# IR-Blue_BT2_PCB.net
KiCad netlist of a schematic drawn in EAGLE
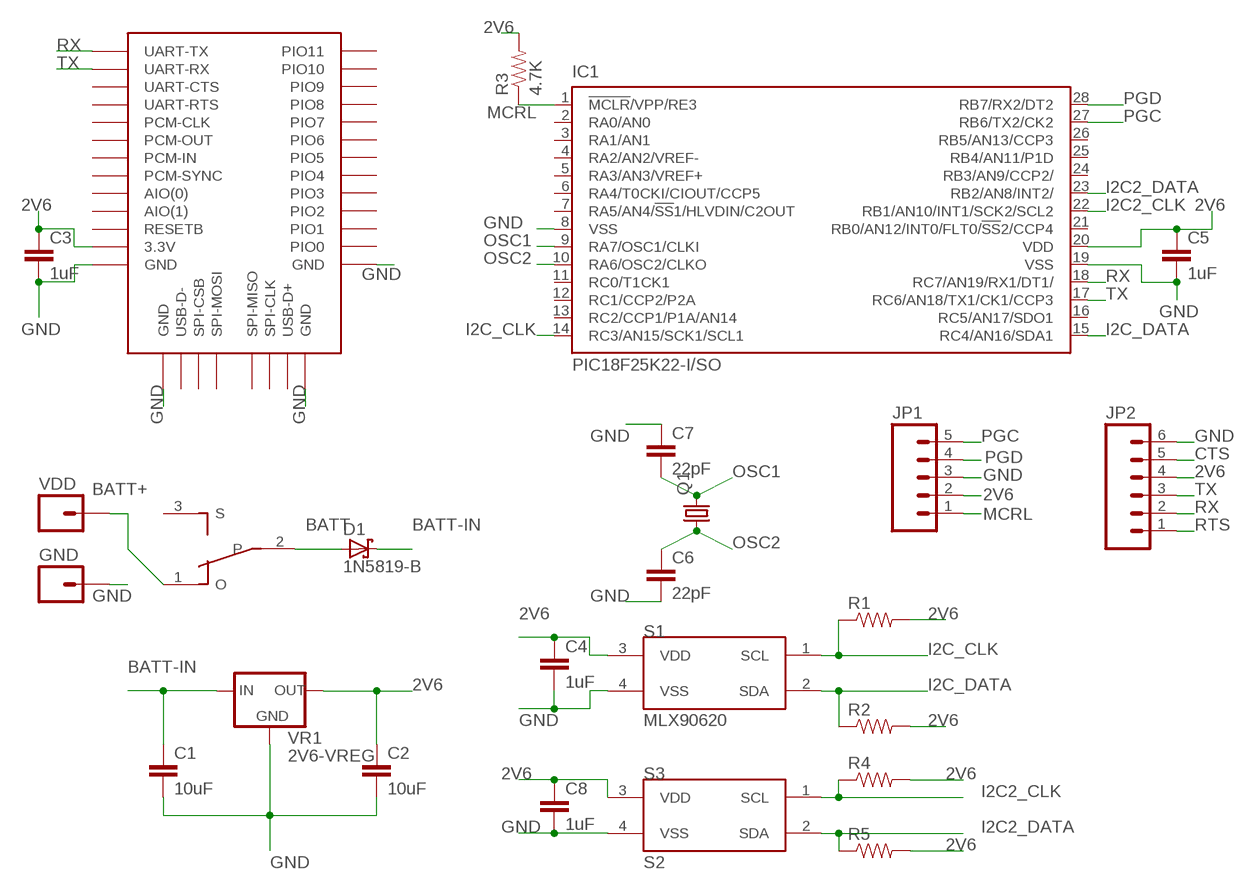
[diagram p0: schematic, sheet 1]

(export (version "E")
  (design (tool "Eeschema 10.0.6"))
  (components
    (comp (ref "C1")
      (value "10uF")
      (footprint "eagle-import:CAP-PTH-5MM")
      (libsource (lib "eagle-import") (part "CAPPTH1"))
    )
    (comp (ref "C2")
      (value "10uF")
      (footprint "eagle-import:CAP-PTH-5MM")
      (libsource (lib "eagle-import") (part "CAPPTH1"))
    )
    (comp (ref "C3")
      (value "1uF")
      (footprint "eagle-import:CAP-PTH-5MM")
      (libsource (lib "eagle-import") (part "CAPPTH1"))
    )
    (comp (ref "C4")
      (value "1uF")
      (footprint "eagle-import:CAP-PTH-5MM")
      (libsource (lib "eagle-import") (part "CAPPTH1"))
    )
    (comp (ref "C5")
      (value "1uF")
      (footprint "eagle-import:CAP-PTH-5MM")
      (libsource (lib "eagle-import") (part "CAPPTH1"))
    )
    (comp (ref "C6")
      (value "22pF")
      (footprint "eagle-import:CAP-PTH-5MM")
      (libsource (lib "eagle-import") (part "CAPPTH1"))
    )
    (comp (ref "C7")
      (value "22pF")
      (footprint "eagle-import:CAP-PTH-5MM")
      (libsource (lib "eagle-import") (part "CAPPTH1"))
    )
    (comp (ref "C8")
      (value "1uF")
      (footprint "eagle-import:CAP-PTH-5MM")
      (libsource (lib "eagle-import") (part "CAPPTH1"))
    )
    (comp (ref "D1")
      (value "1N5819-B")
      (footprint "eagle-import:DO41-7.6")
      (libsource (lib "eagle-import") (part "1N5819-B"))
    )
    (comp (ref "GND")
      (value "M01PTH")
      (footprint "eagle-import:1X01")
      (libsource (lib "eagle-import") (part "M01PTH"))
    )
    (comp (ref "IC1")
      (value "PIC18F25K22-I/SO")
      (footprint "eagle-import:SO28W")
      (libsource (lib "eagle-import") (part "PIC18F25K22/SO-I"))
    )
    (comp (ref "JP1")
      (value "M05PTH")
      (footprint "eagle-import:1X05")
      (libsource (lib "eagle-import") (part "M05PTH"))
    )
    (comp (ref "JP2")
      (value "M06SIP")
      (footprint "eagle-import:1X06")
      (libsource (lib "eagle-import") (part "M06SIP"))
    )
    (comp (ref "Q1")
      (value "CRYSTALHC49S")
      (footprint "eagle-import:HC49_S")
      (libsource (lib "eagle-import") (part "CRYSTALHC49S"))
    )
    (comp (ref "R1")
      (value "RESISTORPTH-1/4W")
      (footprint "eagle-import:AXIAL-0.4")
      (libsource (lib "eagle-import") (part "RESISTORPTH-1/4W"))
    )
    (comp (ref "R2")
      (value "RESISTORPTH-1/4W")
      (footprint "eagle-import:AXIAL-0.4")
      (libsource (lib "eagle-import") (part "RESISTORPTH-1/4W"))
    )
    (comp (ref "R3")
      (value "4.7K")
      (footprint "eagle-import:AXIAL-0.4")
      (libsource (lib "eagle-import") (part "RESISTORPTH-1/4W"))
    )
    (comp (ref "R4")
      (value "RESISTORPTH-1/4W")
      (footprint "eagle-import:AXIAL-0.4")
      (libsource (lib "eagle-import") (part "RESISTORPTH-1/4W"))
    )
    (comp (ref "R5")
      (value "RESISTORPTH-1/4W")
      (footprint "eagle-import:AXIAL-0.4")
      (libsource (lib "eagle-import") (part "RESISTORPTH-1/4W"))
    )
    (comp (ref "S1")
      (value "MLX90620")
      (footprint "eagle-import:TO-39")
      (libsource (lib "eagle-import") (part "MLX90620"))
    )
    (comp (ref "S3")
      (value "S2")
      (footprint "eagle-import:TO-39")
      (libsource (lib "eagle-import") (part "MLX90620"))
    )
    (comp (ref "SW1")
      (value "SMALL_SWITCH")
      (footprint "eagle-import:EG1213")
      (libsource (lib "eagle-import") (part "SMALL_SWITCH"))
    )
    (comp (ref "U$3")
      (value "BTM400_6B")
      (footprint "eagle-import:BTM400_6B")
      (libsource (lib "eagle-import") (part "BTM400_6B"))
    )
    (comp (ref "VDD")
      (value "M01PTH")
      (footprint "eagle-import:1X01")
      (libsource (lib "eagle-import") (part "M01PTH"))
    )
    (comp (ref "VR1")
      (value "2V6-VREG")
      (footprint "eagle-import:TO-92")
      (libsource (lib "eagle-import") (part "2V6-VREG"))
    )
  )
  (nets
    (net (code "1") (name "/2V6") (class "Default")
      (node (ref "C2") (pin "1") (pinfunction "1_1") (pintype "passive"))
      (node (ref "C3") (pin "1") (pinfunction "1_1") (pintype "passive"))
      (node (ref "C4") (pin "1") (pinfunction "1_1") (pintype "passive"))
      (node (ref "C5") (pin "1") (pinfunction "1_1") (pintype "passive"))
      (node (ref "C8") (pin "1") (pinfunction "1_1") (pintype "passive"))
      (node (ref "IC1") (pin "20") (pinfunction "VDD_20") (pintype "power_in"))
      (node (ref "JP1") (pin "2") (pinfunction "2_2") (pintype "passive"))
      (node (ref "JP2") (pin "4") (pinfunction "4_4") (pintype "passive"))
      (node (ref "R1") (pin "P$2") (pinfunction "2_P$2") (pintype "passive"))
      (node (ref "R2") (pin "P$2") (pinfunction "2_P$2") (pintype "passive"))
      (node (ref "R3") (pin "P$2") (pinfunction "2_P$2") (pintype "passive"))
      (node (ref "R4") (pin "P$2") (pinfunction "2_P$2") (pintype "passive"))
      (node (ref "R5") (pin "P$2") (pinfunction "2_P$2") (pintype "passive"))
      (node (ref "S1") (pin "3") (pinfunction "VDD_3") (pintype "bidirectional"))
      (node (ref "S3") (pin "3") (pinfunction "VDD_3") (pintype "bidirectional"))
      (node (ref "U$3") (pin "3.3V") (pinfunction "3.3V_3.3V") (pintype "power_in"))
      (node (ref "VR1") (pin "1") (pinfunction "OUT_1") (pintype "output"))
    )
    (net (code "2") (name "/BATT") (class "Default")
      (node (ref "D1") (pin "A") (pinfunction "A_A") (pintype "passive"))
      (node (ref "SW1") (pin "2") (pinfunction "P_2") (pintype "bidirectional"))
    )
    (net (code "3") (name "/BATT+") (class "Default")
      (node (ref "SW1") (pin "1") (pinfunction "O_1") (pintype "bidirectional"))
      (node (ref "VDD") (pin "1") (pinfunction "1_1") (pintype "passive"))
    )
    (net (code "4") (name "/BATT-IN") (class "Default")
      (node (ref "C1") (pin "1") (pinfunction "1_1") (pintype "passive"))
      (node (ref "D1") (pin "C") (pinfunction "C_C") (pintype "passive"))
      (node (ref "VR1") (pin "3") (pinfunction "IN_3") (pintype "input"))
    )
    (net (code "5") (name "/CTS") (class "Default")
      (node (ref "JP2") (pin "5") (pinfunction "5_5") (pintype "passive"))
    )
    (net (code "6") (name "/GND") (class "Default")
      (node (ref "C1") (pin "2") (pinfunction "2_2") (pintype "passive"))
      (node (ref "C2") (pin "2") (pinfunction "2_2") (pintype "passive"))
      (node (ref "C3") (pin "2") (pinfunction "2_2") (pintype "passive"))
      (node (ref "C4") (pin "2") (pinfunction "2_2") (pintype "passive"))
      (node (ref "C5") (pin "2") (pinfunction "2_2") (pintype "passive"))
      (node (ref "C6") (pin "2") (pinfunction "2_2") (pintype "passive"))
      (node (ref "C7") (pin "1") (pinfunction "1_1") (pintype "passive"))
      (node (ref "C8") (pin "2") (pinfunction "2_2") (pintype "passive"))
      (node (ref "GND") (pin "1") (pinfunction "1_1") (pintype "passive"))
      (node (ref "IC1") (pin "19") (pinfunction "VSS_19") (pintype "power_in"))
      (node (ref "IC1") (pin "8") (pinfunction "VSS_8") (pintype "power_in"))
      (node (ref "JP1") (pin "3") (pinfunction "3_3") (pintype "passive"))
      (node (ref "JP2") (pin "6") (pinfunction "6_6") (pintype "passive"))
      (node (ref "S1") (pin "4") (pinfunction "VSS_4") (pintype "bidirectional"))
      (node (ref "S3") (pin "4") (pinfunction "VSS_4") (pintype "bidirectional"))
      (node (ref "U$3") (pin "GND@1") (pinfunction "GND_GND@1") (pintype "power_in"))
      (node (ref "U$3") (pin "GND@2") (pinfunction "GND_GND@2") (pintype "power_in"))
      (node (ref "U$3") (pin "GND@3") (pinfunction "GND_GND@3") (pintype "power_in"))
      (node (ref "U$3") (pin "GND@4") (pinfunction "GND_GND@4") (pintype "power_in"))
      (node (ref "VR1") (pin "2") (pinfunction "GND_2") (pintype "input"))
    )
    (net (code "7") (name "/I2C2_CLK") (class "Default")
      (node (ref "IC1") (pin "22") (pinfunction "RB1/AN10/INT1/SCK2/SCL2_22") (pintype "bidirectional"))
      (node (ref "R4") (pin "P$1") (pinfunction "1_P$1") (pintype "passive"))
      (node (ref "S3") (pin "1") (pinfunction "SCL_1") (pintype "bidirectional"))
    )
    (net (code "8") (name "/I2C2_DATA") (class "Default")
      (node (ref "IC1") (pin "23") (pinfunction "RB2/AN8/INT2/_23") (pintype "bidirectional"))
      (node (ref "R5") (pin "P$1") (pinfunction "1_P$1") (pintype "passive"))
      (node (ref "S3") (pin "2") (pinfunction "SDA_2") (pintype "bidirectional"))
    )
    (net (code "9") (name "/I2C_CLK") (class "Default")
      (node (ref "IC1") (pin "14") (pinfunction "RC3/AN15/SCK1/SCL1_14") (pintype "bidirectional"))
      (node (ref "R1") (pin "P$1") (pinfunction "1_P$1") (pintype "passive"))
      (node (ref "S1") (pin "1") (pinfunction "SCL_1") (pintype "bidirectional"))
    )
    (net (code "10") (name "/I2C_DATA") (class "Default")
      (node (ref "IC1") (pin "15") (pinfunction "RC4/AN16/SDA1_15") (pintype "bidirectional"))
      (node (ref "R2") (pin "P$1") (pinfunction "1_P$1") (pintype "passive"))
      (node (ref "S1") (pin "2") (pinfunction "SDA_2") (pintype "bidirectional"))
    )
    (net (code "11") (name "/MCRL") (class "Default")
      (node (ref "IC1") (pin "1") (pinfunction "~{MCLR}/VPP/RE3_1") (pintype "input"))
      (node (ref "JP1") (pin "1") (pinfunction "1_1") (pintype "passive"))
      (node (ref "R3") (pin "P$1") (pinfunction "1_P$1") (pintype "passive"))
    )
    (net (code "12") (name "/OSC1") (class "Default")
      (node (ref "C7") (pin "2") (pinfunction "2_2") (pintype "passive"))
      (node (ref "IC1") (pin "9") (pinfunction "RA7/OSC1/CLKI_9") (pintype "input"))
      (node (ref "Q1") (pin "2") (pinfunction "2_2") (pintype "passive"))
    )
    (net (code "13") (name "/OSC2") (class "Default")
      (node (ref "C6") (pin "1") (pinfunction "1_1") (pintype "passive"))
      (node (ref "IC1") (pin "10") (pinfunction "RA6/OSC2/CLKO_10") (pintype "output"))
      (node (ref "Q1") (pin "1") (pinfunction "1_1") (pintype "passive"))
    )
    (net (code "14") (name "/PGC") (class "Default")
      (node (ref "IC1") (pin "27") (pinfunction "RB6/TX2/CK2_27") (pintype "bidirectional"))
      (node (ref "JP1") (pin "5") (pinfunction "5_5") (pintype "passive"))
    )
    (net (code "15") (name "/PGD") (class "Default")
      (node (ref "IC1") (pin "28") (pinfunction "RB7/RX2/DT2_28") (pintype "bidirectional"))
      (node (ref "JP1") (pin "4") (pinfunction "4_4") (pintype "passive"))
    )
    (net (code "16") (name "/RTS") (class "Default")
      (node (ref "JP2") (pin "1") (pinfunction "1_1") (pintype "passive"))
    )
    (net (code "17") (name "/RX") (class "Default")
      (node (ref "IC1") (pin "18") (pinfunction "RC7/AN19/RX1/DT1/_18") (pintype "bidirectional"))
      (node (ref "JP2") (pin "2") (pinfunction "2_2") (pintype "passive"))
      (node (ref "U$3") (pin "UART-TX") (pinfunction "UART-TX_UART-TX") (pintype "bidirectional"))
    )
    (net (code "18") (name "/TX") (class "Default")
      (node (ref "IC1") (pin "17") (pinfunction "RC6/AN18/TX1/CK1/CCP3_17") (pintype "bidirectional"))
      (node (ref "JP2") (pin "3") (pinfunction "3_3") (pintype "passive"))
      (node (ref "U$3") (pin "UART-RX") (pinfunction "UART-RX_UART-RX") (pintype "bidirectional"))
    )
    (net (code "19") (name "unconnected-(IC1-RA0{slash}AN0-Pad2)") (class "Default")
      (node (ref "IC1") (pin "2") (pinfunction "RA0/AN0_2") (pintype "bidirectional"))
    )
    (net (code "20") (name "unconnected-(IC1-RA1{slash}AN1-Pad3)") (class "Default")
      (node (ref "IC1") (pin "3") (pinfunction "RA1/AN1_3") (pintype "bidirectional"))
    )
    (net (code "21") (name "unconnected-(IC1-RA2{slash}AN2{slash}VREF--Pad4)") (class "Default")
      (node (ref "IC1") (pin "4") (pinfunction "RA2/AN2/VREF-_4") (pintype "bidirectional"))
    )
    (net (code "22") (name "unconnected-(IC1-RA3{slash}AN3{slash}VREF+-Pad5)") (class "Default")
      (node (ref "IC1") (pin "5") (pinfunction "RA3/AN3/VREF+_5") (pintype "bidirectional"))
    )
    (net (code "23") (name "unconnected-(IC1-RA4{slash}T0CKI{slash}CIOUT{slash}CCP5-Pad6)") (class "Default")
      (node (ref "IC1") (pin "6") (pinfunction "RA4/T0CKI/CIOUT/CCP5_6") (pintype "bidirectional"))
    )
    (net (code "24") (name "unconnected-(IC1-RA5{slash}AN4{slash}~{SS}1{slash}HLVDIN{slash}C2OUT-Pad7)") (class "Default")
      (node (ref "IC1") (pin "7") (pinfunction "RA5/AN4/~{SS}1/HLVDIN/C2OUT_7") (pintype "bidirectional"))
    )
    (net (code "25") (name "unconnected-(IC1-RB0{slash}AN12{slash}INT0{slash}FLT0{slash}~{SS}2{slash}CCP4-Pad21)") (class "Default")
      (node (ref "IC1") (pin "21") (pinfunction "RB0/AN12/INT0/FLT0/~{SS}2/CCP4_21") (pintype "bidirectional"))
    )
    (net (code "26") (name "unconnected-(IC1-RB3{slash}AN9{slash}CCP2{slash}-Pad24)") (class "Default")
      (node (ref "IC1") (pin "24") (pinfunction "RB3/AN9/CCP2/_24") (pintype "bidirectional"))
    )
    (net (code "27") (name "unconnected-(IC1-RB4{slash}AN11{slash}P1D-Pad25)") (class "Default")
      (node (ref "IC1") (pin "25") (pinfunction "RB4/AN11/P1D_25") (pintype "bidirectional"))
    )
    (net (code "28") (name "unconnected-(IC1-RB5{slash}AN13{slash}CCP3-Pad26)") (class "Default")
      (node (ref "IC1") (pin "26") (pinfunction "RB5/AN13/CCP3_26") (pintype "bidirectional"))
    )
    (net (code "29") (name "unconnected-(IC1-RC0{slash}T1CK1-Pad11)") (class "Default")
      (node (ref "IC1") (pin "11") (pinfunction "RC0/T1CK1_11") (pintype "bidirectional"))
    )
    (net (code "30") (name "unconnected-(IC1-RC1{slash}CCP2{slash}P2A-Pad12)") (class "Default")
      (node (ref "IC1") (pin "12") (pinfunction "RC1/CCP2/P2A_12") (pintype "bidirectional"))
    )
    (net (code "31") (name "unconnected-(IC1-RC2{slash}CCP1{slash}P1A{slash}AN14-Pad13)") (class "Default")
      (node (ref "IC1") (pin "13") (pinfunction "RC2/CCP1/P1A/AN14_13") (pintype "bidirectional"))
    )
    (net (code "32") (name "unconnected-(IC1-RC5{slash}AN17{slash}SDO1-Pad16)") (class "Default")
      (node (ref "IC1") (pin "16") (pinfunction "RC5/AN17/SDO1_16") (pintype "bidirectional"))
    )
    (net (code "33") (name "unconnected-(SW1-S-Pad3)") (class "Default")
      (node (ref "SW1") (pin "3") (pinfunction "S_3") (pintype "bidirectional"))
    )
    (net (code "34") (name "unconnected-(U$3-PIO0-PadPIO(0))") (class "Default")
      (node (ref "U$3") (pin "PIO(0)") (pinfunction "PIO0_PIO(0)") (pintype "bidirectional"))
    )
    (net (code "35") (name "unconnected-(U$3-PIO1-PadPIO(1))") (class "Default")
      (node (ref "U$3") (pin "PIO(1)") (pinfunction "PIO1_PIO(1)") (pintype "bidirectional"))
    )
    (net (code "36") (name "unconnected-(U$3-PIO2-PadPIO(2))") (class "Default")
      (node (ref "U$3") (pin "PIO(2)") (pinfunction "PIO2_PIO(2)") (pintype "bidirectional"))
    )
    (net (code "37") (name "unconnected-(U$3-PIO3-PadPIO(3))") (class "Default")
      (node (ref "U$3") (pin "PIO(3)") (pinfunction "PIO3_PIO(3)") (pintype "bidirectional"))
    )
    (net (code "38") (name "unconnected-(U$3-PIO4-PadPIO(4))") (class "Default")
      (node (ref "U$3") (pin "PIO(4)") (pinfunction "PIO4_PIO(4)") (pintype "bidirectional"))
    )
    (net (code "39") (name "unconnected-(U$3-PIO5-PadPIO(5))") (class "Default")
      (node (ref "U$3") (pin "PIO(5)") (pinfunction "PIO5_PIO(5)") (pintype "bidirectional"))
    )
    (net (code "40") (name "unconnected-(U$3-PIO6-PadPIO(6))") (class "Default")
      (node (ref "U$3") (pin "PIO(6)") (pinfunction "PIO6_PIO(6)") (pintype "bidirectional"))
    )
    (net (code "41") (name "unconnected-(U$3-PIO7-PadPIO(7))") (class "Default")
      (node (ref "U$3") (pin "PIO(7)") (pinfunction "PIO7_PIO(7)") (pintype "bidirectional"))
    )
    (net (code "42") (name "unconnected-(U$3-PIO8-PadPIO(8))") (class "Default")
      (node (ref "U$3") (pin "PIO(8)") (pinfunction "PIO8_PIO(8)") (pintype "bidirectional"))
    )
    (net (code "43") (name "unconnected-(U$3-PIO9-PadPIO(9))") (class "Default")
      (node (ref "U$3") (pin "PIO(9)") (pinfunction "PIO9_PIO(9)") (pintype "bidirectional"))
    )
    (net (code "44") (name "unconnected-(U$3-PIO10-PadPIO(10))") (class "Default")
      (node (ref "U$3") (pin "PIO(10)") (pinfunction "PIO10_PIO(10)") (pintype "bidirectional"))
    )
    (net (code "45") (name "unconnected-(U$3-PIO11-PadPIO(11))") (class "Default")
      (node (ref "U$3") (pin "PIO(11)") (pinfunction "PIO11_PIO(11)") (pintype "bidirectional"))
    )
    (net (code "46") (name "unconnected-(U$3-PadAIO(0))") (class "Default")
      (node (ref "U$3") (pin "AIO(0)") (pinfunction "AIO(0)_AIO(0)") (pintype "bidirectional"))
    )
    (net (code "47") (name "unconnected-(U$3-PadAIO(1))") (class "Default")
      (node (ref "U$3") (pin "AIO(1)") (pinfunction "AIO(1)_AIO(1)") (pintype "bidirectional"))
    )
    (net (code "48") (name "unconnected-(U$3-PadPCM-CLK)") (class "Default")
      (node (ref "U$3") (pin "PCM-CLK") (pinfunction "PCM-CLK_PCM-CLK") (pintype "bidirectional"))
    )
    (net (code "49") (name "unconnected-(U$3-PadPCM-IN)") (class "Default")
      (node (ref "U$3") (pin "PCM-IN") (pinfunction "PCM-IN_PCM-IN") (pintype "bidirectional"))
    )
    (net (code "50") (name "unconnected-(U$3-PadPCM-OUT)") (class "Default")
      (node (ref "U$3") (pin "PCM-OUT") (pinfunction "PCM-OUT_PCM-OUT") (pintype "bidirectional"))
    )
    (net (code "51") (name "unconnected-(U$3-PadPCM-SYNC)") (class "Default")
      (node (ref "U$3") (pin "PCM-SYNC") (pinfunction "PCM-SYNC_PCM-SYNC") (pintype "bidirectional"))
    )
    (net (code "52") (name "unconnected-(U$3-PadRESETB)") (class "Default")
      (node (ref "U$3") (pin "RESETB") (pinfunction "RESETB_RESETB") (pintype "bidirectional"))
    )
    (net (code "53") (name "unconnected-(U$3-PadSPI-CLK)") (class "Default")
      (node (ref "U$3") (pin "SPI-CLK") (pinfunction "SPI-CLK_SPI-CLK") (pintype "bidirectional"))
    )
    (net (code "54") (name "unconnected-(U$3-PadSPI-CSB)") (class "Default")
      (node (ref "U$3") (pin "SPI-CSB") (pinfunction "SPI-CSB_SPI-CSB") (pintype "bidirectional"))
    )
    (net (code "55") (name "unconnected-(U$3-PadSPI-MISO)") (class "Default")
      (node (ref "U$3") (pin "SPI-MISO") (pinfunction "SPI-MISO_SPI-MISO") (pintype "bidirectional"))
    )
    (net (code "56") (name "unconnected-(U$3-PadSPI-MOSI)") (class "Default")
      (node (ref "U$3") (pin "SPI-MOSI") (pinfunction "SPI-MOSI_SPI-MOSI") (pintype "bidirectional"))
    )
    (net (code "57") (name "unconnected-(U$3-PadUART-CTS)") (class "Default")
      (node (ref "U$3") (pin "UART-CTS") (pinfunction "UART-CTS_UART-CTS") (pintype "bidirectional"))
    )
    (net (code "58") (name "unconnected-(U$3-PadUART-RTS)") (class "Default")
      (node (ref "U$3") (pin "UART-RTS") (pinfunction "UART-RTS_UART-RTS") (pintype "bidirectional"))
    )
    (net (code "59") (name "unconnected-(U$3-PadUSB-D+)") (class "Default")
      (node (ref "U$3") (pin "USB-D+") (pinfunction "USB-D+_USB-D+") (pintype "bidirectional"))
    )
    (net (code "60") (name "unconnected-(U$3-PadUSB-D-)") (class "Default")
      (node (ref "U$3") (pin "USB-D-") (pinfunction "USB-D-_USB-D-") (pintype "bidirectional"))
    )
  )
)
